# Sheet1.net
KiCad netlist of a schematic drawn in Altium Designer
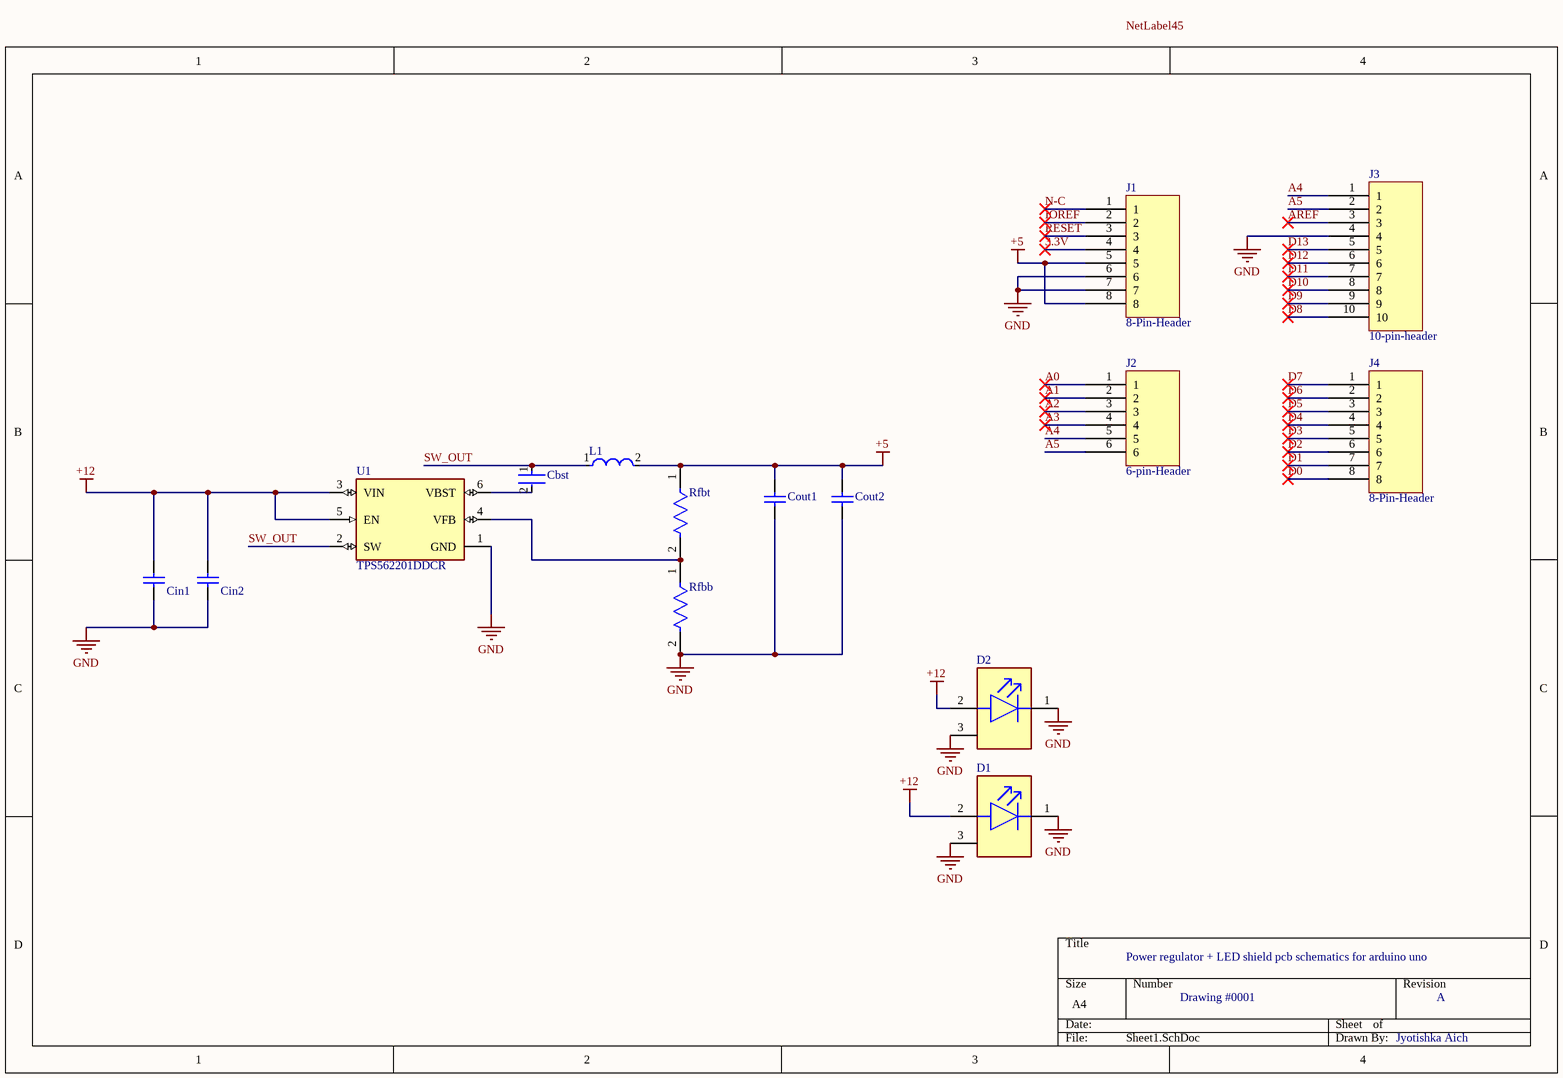
[diagram p0: Sheet1.SchDoc]

(export (version "E")
  (design (tool "Eeschema 10.0.6"))
  (components
    (comp (ref "Cbst")
      (value "CC0805KRX7R8BB104")
      (footprint "FP-CC0805-0_85-MFG")
      (description "CAP CER 0.1UF 25V X7R 0805")
      (fields (field (name "TOLERANCE") "0.1") (field (name "MANUFACTURER") "Yageo"))
      (libsource (lib "Altium Content Vault") (part "11868f565c42a9108669ba33697ecf6"))
    )
    (comp (ref "Cin1")
      (value "GRM31CR61E106KA12L")
      (footprint "CAPC3216X180X55ML20T25")
      (description "Chip Capacitor, 10 uF, +/- 10%, 25 V, -55 to 85 degC, 1206 (3216 Metric), RoHS, Tape and Reel")
      (fields (field (name "MANUFACTURER") "Murata") (field (name "TOLERANCE") "10%"))
      (libsource (lib "Altium Content Vault") (part "CAP-NP-2"))
    )
    (comp (ref "Cin2")
      (value "GRM31CR61E106KA12L")
      (footprint "CAPC3216X180X55ML20T25")
      (description "Chip Capacitor, 10 uF, +/- 10%, 25 V, -55 to 85 degC, 1206 (3216 Metric), RoHS, Tape and Reel")
      (fields (field (name "MANUFACTURER") "Murata") (field (name "TOLERANCE") "10%"))
      (libsource (lib "Altium Content Vault") (part "CAP-NP-2"))
    )
    (comp (ref "Cout1")
      (value "C1608X5R1A226M080AC")
      (footprint "CAPC1608X100X20ML10")
      (description "Chip Capacitor, 22 uF, +/- 20%, 10 V, -55 to 85 degC, 0603 (1608 Metric), RoHS, Tape and Reel")
      (fields (field (name "MANUFACTURER") "TDK") (field (name "TOLERANCE") "±20%"))
      (libsource (lib "Altium Content Vault") (part "CAP-NP-2"))
    )
    (comp (ref "Cout2")
      (value "C1608X5R1A226M080AC")
      (footprint "CAPC1608X100X20ML10")
      (description "Chip Capacitor, 22 uF, +/- 20%, 10 V, -55 to 85 degC, 0603 (1608 Metric), RoHS, Tape and Reel")
      (fields (field (name "MANUFACTURER") "TDK") (field (name "TOLERANCE") "±20%"))
      (libsource (lib "Altium Content Vault") (part "CAP-NP-2"))
    )
    (comp (ref "D1")
      (value "LXR7-SW30")
      (footprint "FP-LXR7-SW30-MFG")
      (description "LED LUXEON WARM WHITE 3000K 2SMD")
      (fields
        (field (name "OCTOPART") "https://octopart.com/lxr7-sw30-philips+lumileds-23267781")
        (field (name "MANUFACTURER") "Philips Lumileds")
      )
      (libsource (lib "Altium Content Vault") (part "15abf66421794e835061b1b870413f4"))
    )
    (comp (ref "D2")
      (value "LXR7-SW30")
      (footprint "FP-LXR7-SW30-MFG")
      (description "LED LUXEON WARM WHITE 3000K 2SMD")
      (fields
        (field (name "OCTOPART") "https://octopart.com/lxr7-sw30-philips+lumileds-23267781")
        (field (name "MANUFACTURER") "Philips Lumileds")
      )
      (libsource (lib "Altium Content Vault") (part "15abf66421794e835061b1b870413f4"))
    )
    (comp (ref "J1")
      (value "8-Pin-Header")
      (footprint "8-Pin-Header-Footprint-1")
      (libsource (lib "Vellore Institute of Technology, Chennai") (part "8-Pin-Header"))
    )
    (comp (ref "J2")
      (value "6-pin-Header")
      (footprint "6-pin-Header-Footprint")
      (libsource (lib "Vellore Institute of Technology, Chennai") (part "6-Pin-Header"))
    )
    (comp (ref "J3")
      (value "10-pin-header")
      (footprint "10-pin-header-Footprint-1")
      (libsource (lib "Vellore Institute of Technology, Chennai") (part "10-pin-header-Symbol"))
    )
    (comp (ref "J4")
      (value "8-Pin-Header")
      (footprint "8-Pin-Header-Footprint-1")
      (libsource (lib "Vellore Institute of Technology, Chennai") (part "8-Pin-Header"))
    )
    (comp (ref "L1")
      (value "NRS8030T3R3MJGJ")
      (footprint "FP-NRS8030-MFG")
      (description "Inductor Power Shielded Wirewound 3.3uH 20% 100KHz Ferrite 4.2A 24.7mΩ DCR T/R")
      (fields (field (name "TOLERANCE") "20%"))
      (libsource (lib "Altium Content Vault") (part "725321dda6339637d4d059423bc1c3c"))
    )
    (comp (ref "Rfbb")
      (value "CRCW040210K0FKED")
      (footprint "FP-CRCW0402-e3-IPC_B")
      (description "RES SMD 10K OHM 1% 1/16W 0402")
      (fields (field (name "TOLERANCE") "1%"))
      (libsource (lib "Altium Content Vault") (part "1029c3af85768c4190bb7ad29bc67b5"))
    )
    (comp (ref "Rfbt")
      (value "AC0402FR-0756K2L")
      (footprint "FP-AC0402-IPC_B")
      (description "RES 56.2kΩ ±1% 0.063W 0402")
      (fields (field (name "TOLERANCE") "1%"))
      (libsource (lib "Altium Content Vault") (part "1029c3af85768c4190bb7ad29bc67b5"))
    )
    (comp (ref "U1")
      (value "TPS562201DDCR")
      (footprint "FP-DDC0006A-IPC_C")
      (description "Switching Regulator, 2A, 580kHz Switching Freq-Max, PDSO6")
      (libsource (lib "Vellore Institute of Technology, Chennai") (part "957e164956730ea4bf6293280af19fc"))
    )
  )
  (nets
    (net (code "1") (name "+5") (class "Default")
      (node (ref "Cout1") (pin "1") (pinfunction "1_1") (pintype "passive"))
      (node (ref "Cout2") (pin "1") (pinfunction "1_1") (pintype "passive"))
      (node (ref "J1") (pin "5") (pinfunction "5_5") (pintype "passive"))
      (node (ref "J1") (pin "8") (pinfunction "8_8") (pintype "passive"))
      (node (ref "L1") (pin "2") (pinfunction "2_2") (pintype "passive"))
      (node (ref "Rfbt") (pin "1") (pinfunction "1_1") (pintype "passive"))
    )
    (net (code "2") (name "+12") (class "Default")
      (node (ref "Cin1") (pin "1") (pinfunction "1_1") (pintype "passive"))
      (node (ref "Cin2") (pin "1") (pinfunction "1_1") (pintype "passive"))
      (node (ref "D1") (pin "2") (pinfunction "A_2") (pintype "passive"))
      (node (ref "D2") (pin "2") (pinfunction "A_2") (pintype "passive"))
      (node (ref "U1") (pin "3") (pinfunction "VIN_3") (pintype "bidirectional"))
      (node (ref "U1") (pin "5") (pinfunction "EN_5") (pintype "input"))
    )
    (net (code "3") (name "/3.3V") (class "Default")
      (node (ref "J1") (pin "4") (pinfunction "4_4") (pintype "passive+no_connect"))
    )
    (net (code "4") (name "/A0") (class "Default")
      (node (ref "J2") (pin "1") (pinfunction "1_1") (pintype "passive+no_connect"))
    )
    (net (code "5") (name "/A1") (class "Default")
      (node (ref "J2") (pin "2") (pinfunction "2_2") (pintype "passive+no_connect"))
    )
    (net (code "6") (name "/A2") (class "Default")
      (node (ref "J2") (pin "3") (pinfunction "3_3") (pintype "passive+no_connect"))
    )
    (net (code "7") (name "/A3") (class "Default")
      (node (ref "J2") (pin "4") (pinfunction "4_4") (pintype "passive+no_connect"))
    )
    (net (code "8") (name "/A4") (class "Default")
      (node (ref "J2") (pin "5") (pinfunction "5_5") (pintype "passive"))
      (node (ref "J3") (pin "1") (pinfunction "1_1") (pintype "passive"))
    )
    (net (code "9") (name "/A5") (class "Default")
      (node (ref "J2") (pin "6") (pinfunction "6_6") (pintype "passive"))
      (node (ref "J3") (pin "2") (pinfunction "2_2") (pintype "passive"))
    )
    (net (code "10") (name "/AREF") (class "Default")
      (node (ref "J3") (pin "3") (pinfunction "3_3") (pintype "passive+no_connect"))
    )
    (net (code "11") (name "/D0") (class "Default")
      (node (ref "J4") (pin "8") (pinfunction "8_8") (pintype "passive+no_connect"))
    )
    (net (code "12") (name "/D1") (class "Default")
      (node (ref "J4") (pin "7") (pinfunction "7_7") (pintype "passive+no_connect"))
    )
    (net (code "13") (name "/D2") (class "Default")
      (node (ref "J4") (pin "6") (pinfunction "6_6") (pintype "passive+no_connect"))
    )
    (net (code "14") (name "/D3") (class "Default")
      (node (ref "J4") (pin "5") (pinfunction "5_5") (pintype "passive+no_connect"))
    )
    (net (code "15") (name "/D4") (class "Default")
      (node (ref "J4") (pin "4") (pinfunction "4_4") (pintype "passive+no_connect"))
    )
    (net (code "16") (name "/D5") (class "Default")
      (node (ref "J4") (pin "3") (pinfunction "3_3") (pintype "passive+no_connect"))
    )
    (net (code "17") (name "/D6") (class "Default")
      (node (ref "J4") (pin "2") (pinfunction "2_2") (pintype "passive+no_connect"))
    )
    (net (code "18") (name "/D7") (class "Default")
      (node (ref "J4") (pin "1") (pinfunction "1_1") (pintype "passive+no_connect"))
    )
    (net (code "19") (name "/D8") (class "Default")
      (node (ref "J3") (pin "10") (pinfunction "10_10") (pintype "passive+no_connect"))
    )
    (net (code "20") (name "/D9") (class "Default")
      (node (ref "J3") (pin "9") (pinfunction "9_9") (pintype "passive+no_connect"))
    )
    (net (code "21") (name "/D10") (class "Default")
      (node (ref "J3") (pin "8") (pinfunction "8_8") (pintype "passive+no_connect"))
    )
    (net (code "22") (name "/D11") (class "Default")
      (node (ref "J3") (pin "7") (pinfunction "7_7") (pintype "passive+no_connect"))
    )
    (net (code "23") (name "/D12") (class "Default")
      (node (ref "J3") (pin "6") (pinfunction "6_6") (pintype "passive+no_connect"))
    )
    (net (code "24") (name "/D13") (class "Default")
      (node (ref "J3") (pin "5") (pinfunction "5_5") (pintype "passive+no_connect"))
    )
    (net (code "25") (name "/IOREF") (class "Default")
      (node (ref "J1") (pin "2") (pinfunction "2_2") (pintype "passive+no_connect"))
    )
    (net (code "26") (name "/N-C") (class "Default")
      (node (ref "J1") (pin "1") (pinfunction "1_1") (pintype "passive+no_connect"))
    )
    (net (code "28") (name "/RESET") (class "Default")
      (node (ref "J1") (pin "3") (pinfunction "3_3") (pintype "passive+no_connect"))
    )
    (net (code "29") (name "/SW_OUT") (class "Default")
      (node (ref "Cbst") (pin "1") (pinfunction "1_1") (pintype "passive"))
      (node (ref "L1") (pin "1") (pinfunction "1_1") (pintype "passive"))
      (node (ref "U1") (pin "2") (pinfunction "SW_2") (pintype "bidirectional"))
    )
    (net (code "30") (name "GND") (class "Default")
      (node (ref "Cin1") (pin "2") (pinfunction "2_2") (pintype "passive"))
      (node (ref "Cin2") (pin "2") (pinfunction "2_2") (pintype "passive"))
      (node (ref "Cout1") (pin "2") (pinfunction "2_2") (pintype "passive"))
      (node (ref "Cout2") (pin "2") (pinfunction "2_2") (pintype "passive"))
      (node (ref "D1") (pin "1") (pinfunction "C_1") (pintype "passive"))
      (node (ref "D1") (pin "3") (pinfunction "THERMAL_PAD_3") (pintype "passive"))
      (node (ref "D2") (pin "1") (pinfunction "C_1") (pintype "passive"))
      (node (ref "D2") (pin "3") (pinfunction "THERMAL_PAD_3") (pintype "passive"))
      (node (ref "J1") (pin "6") (pinfunction "6_6") (pintype "passive"))
      (node (ref "J1") (pin "7") (pinfunction "7_7") (pintype "passive"))
      (node (ref "J3") (pin "4") (pinfunction "4_4") (pintype "passive"))
      (node (ref "Rfbb") (pin "2") (pinfunction "2_2") (pintype "passive"))
      (node (ref "U1") (pin "1") (pinfunction "GND_1") (pintype "power_in"))
    )
    (net (code "31") (name "Net-(U1-VBST)") (class "Default")
      (node (ref "Cbst") (pin "2") (pinfunction "2_2") (pintype "passive"))
      (node (ref "U1") (pin "6") (pinfunction "VBST_6") (pintype "bidirectional"))
    )
    (net (code "32") (name "Net-(U1-VFB)") (class "Default")
      (node (ref "Rfbb") (pin "1") (pinfunction "1_1") (pintype "passive"))
      (node (ref "Rfbt") (pin "2") (pinfunction "2_2") (pintype "passive"))
      (node (ref "U1") (pin "4") (pinfunction "VFB_4") (pintype "bidirectional"))
    )
  )
)
